# sx19_project_02_air_quality.net
KiCad netlist of a schematic drawn in EAGLE
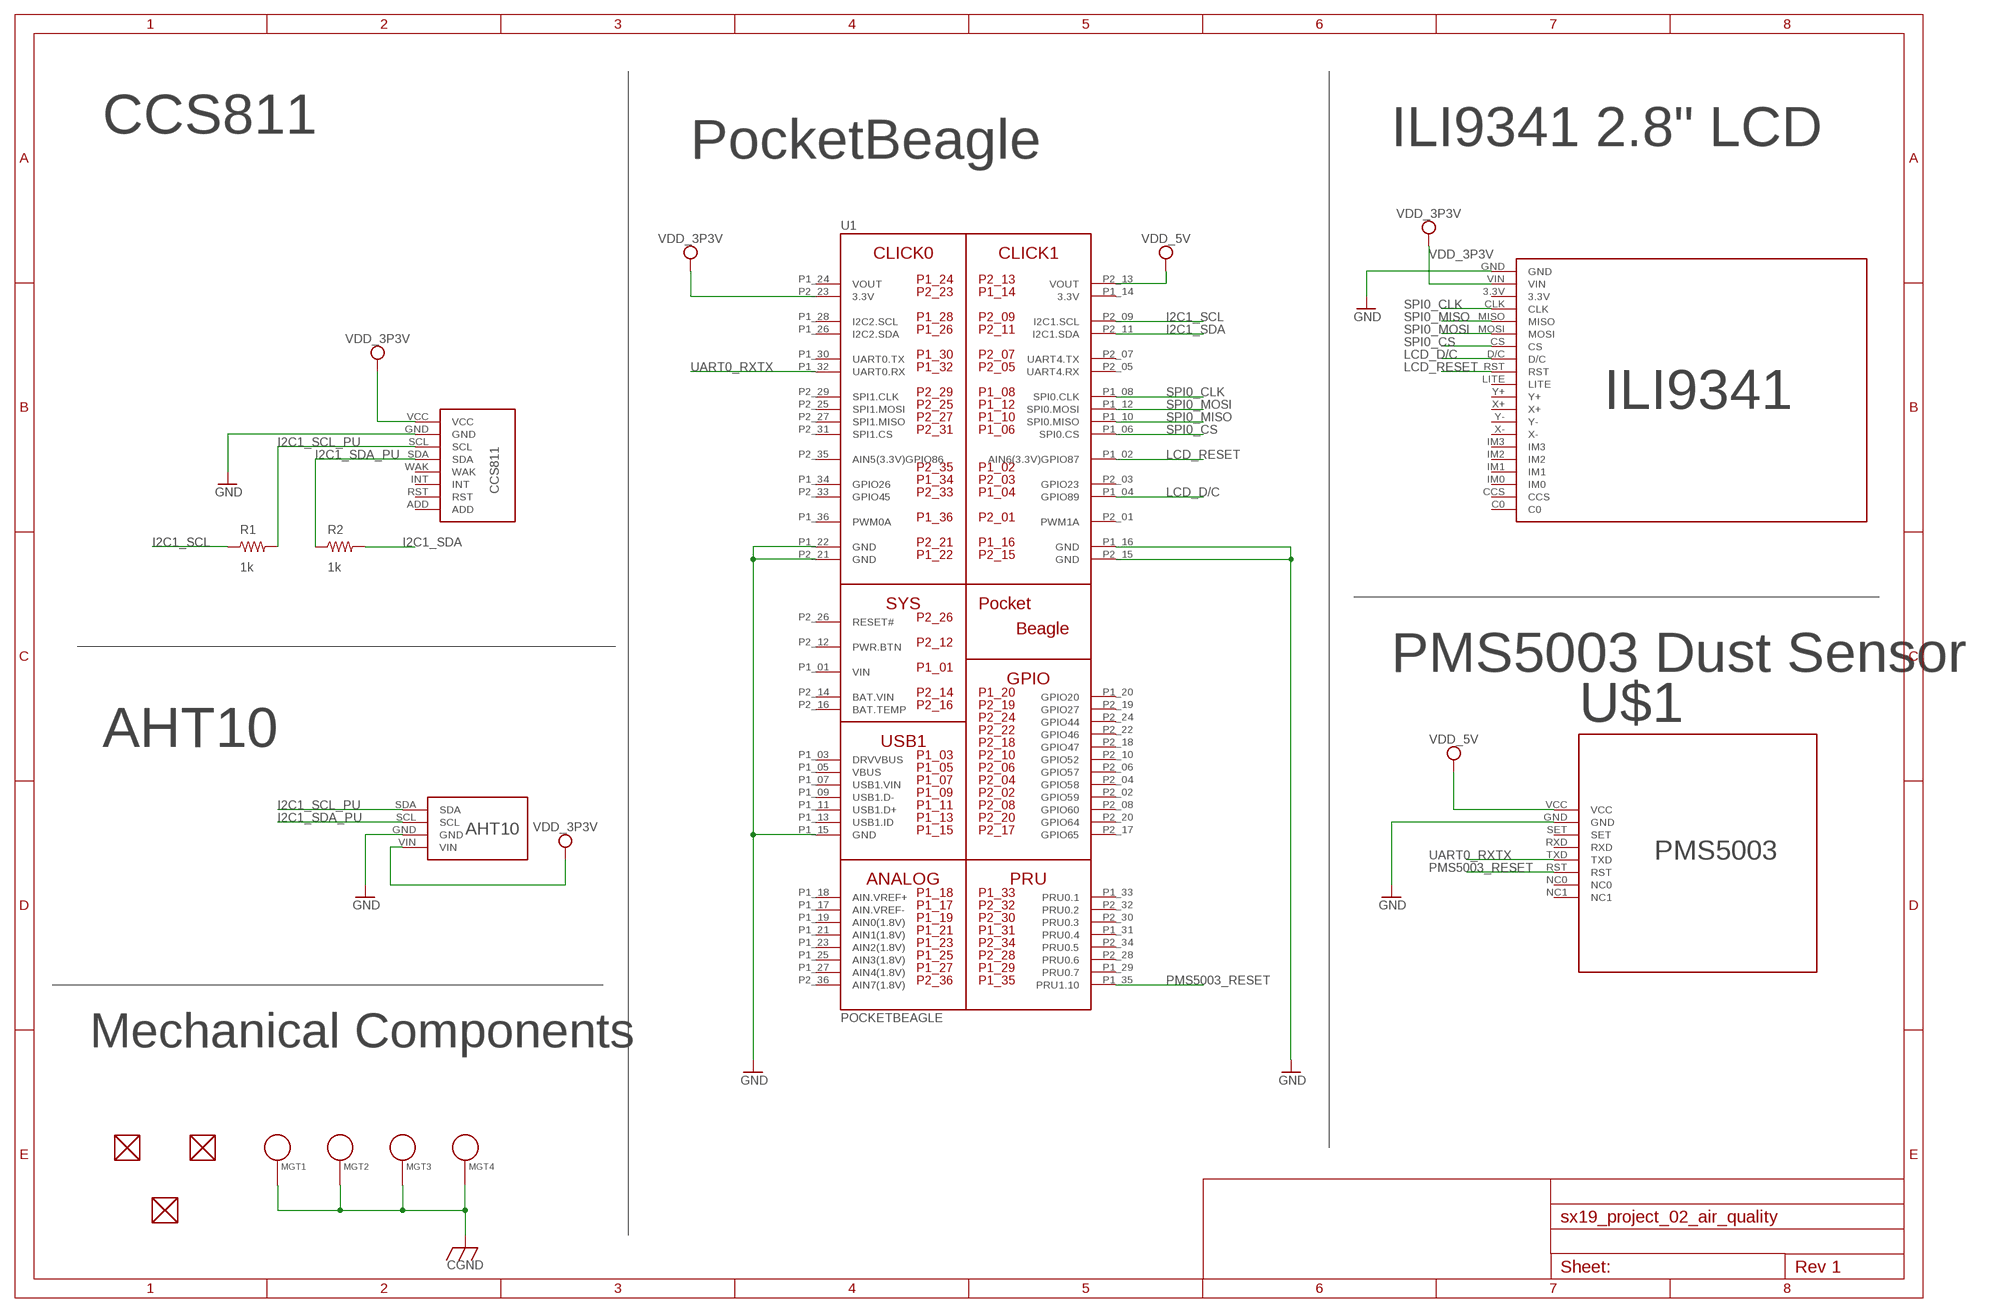
[diagram p0: schematic, sheet 1]

(export (version "E")
  (design (tool "Eeschema 10.0.6"))
  (components
    (comp (ref "B1")
      (value "AHT10")
      (footprint "eagle-import:AHT10")
      (libsource (lib "eagle-import") (part "AHT10"))
    )
    (comp (ref "B2")
      (value "CCS811")
      (footprint "eagle-import:CCS811")
      (libsource (lib "eagle-import") (part "CCS811"))
    )
    (comp (ref "B3")
      (value "ILI9341")
      (footprint "eagle-import:ILI9341")
      (libsource (lib "eagle-import") (part "ILI9341"))
    )
    (comp (ref "FUD1")
      (value "FIDUCIAL")
      (footprint "eagle-import:FIDUCIAL_40MIL")
      (libsource (lib "eagle-import") (part "FIDUCIAL"))
    )
    (comp (ref "FUD2")
      (value "FIDUCIAL")
      (footprint "eagle-import:FIDUCIAL_40MIL")
      (libsource (lib "eagle-import") (part "FIDUCIAL"))
    )
    (comp (ref "FUD3")
      (value "FIDUCIAL")
      (footprint "eagle-import:FIDUCIAL_40MIL")
      (libsource (lib "eagle-import") (part "FIDUCIAL"))
    )
    (comp (ref "MGT1")
      (value "MOUNTING_HOLE")
      (footprint "eagle-import:MOUNTING_HOLE")
      (libsource (lib "eagle-import") (part "MOUNTING_HOLE"))
    )
    (comp (ref "MGT2")
      (value "MOUNTING_HOLE")
      (footprint "eagle-import:MOUNTING_HOLE")
      (libsource (lib "eagle-import") (part "MOUNTING_HOLE"))
    )
    (comp (ref "MGT3")
      (value "MOUNTING_HOLE")
      (footprint "eagle-import:MOUNTING_HOLE")
      (libsource (lib "eagle-import") (part "MOUNTING_HOLE"))
    )
    (comp (ref "MGT4")
      (value "MOUNTING_HOLE")
      (footprint "eagle-import:MOUNTING_HOLE")
      (libsource (lib "eagle-import") (part "MOUNTING_HOLE"))
    )
    (comp (ref "R1")
      (value "1k")
      (footprint "eagle-import:R0603")
      (libsource (lib "eagle-import") (part "R_R0603"))
    )
    (comp (ref "R2")
      (value "1k")
      (footprint "eagle-import:R0603")
      (libsource (lib "eagle-import") (part "R_R0603"))
    )
    (comp (ref "U$1")
      (value "PMS5003")
      (footprint "eagle-import:PMS5003")
      (libsource (lib "eagle-import") (part "PMS5003"))
    )
    (comp (ref "U1")
      (value "POCKETBEAGLE")
      (footprint "eagle-import:POCKETBEAGLE")
      (libsource (lib "eagle-import") (part "POCKETBEAGLE"))
    )
  )
  (nets
    (net (code "1") (name "/3.3V") (class "Default")
      (node (ref "U1") (pin "P1_14") (pinfunction "3.3V_P1_14") (pintype "power_in"))
    )
    (net (code "2") (name "/BAT.VIN") (class "Default")
      (node (ref "U1") (pin "P2_14") (pinfunction "BAT.VIN_P2_14") (pintype "power_in"))
    )
    (net (code "3") (name "/I2C1_SCL") (class "Default")
      (node (ref "R1") (pin "1") (pinfunction "1_1") (pintype "passive"))
      (node (ref "U1") (pin "P2_09") (pinfunction "I2C1.SCL_P2_09") (pintype "bidirectional"))
    )
    (net (code "4") (name "/I2C1_SCL_PU") (class "Default")
      (node (ref "B1") (pin "SDA") (pinfunction "SDA_SDA") (pintype "bidirectional"))
      (node (ref "B2") (pin "SCL") (pinfunction "SCL_SCL") (pintype "bidirectional"))
      (node (ref "R1") (pin "2") (pinfunction "2_2") (pintype "passive"))
    )
    (net (code "5") (name "/I2C1_SDA") (class "Default")
      (node (ref "R2") (pin "2") (pinfunction "2_2") (pintype "passive"))
      (node (ref "U1") (pin "P2_11") (pinfunction "I2C1.SDA_P2_11") (pintype "bidirectional"))
    )
    (net (code "6") (name "/I2C1_SDA_PU") (class "Default")
      (node (ref "B1") (pin "SCL") (pinfunction "SCL_SCL") (pintype "bidirectional"))
      (node (ref "B2") (pin "SDA") (pinfunction "SDA_SDA") (pintype "bidirectional"))
      (node (ref "R2") (pin "1") (pinfunction "1_1") (pintype "passive"))
    )
    (net (code "7") (name "/LCD_D{slash}C") (class "Default")
      (node (ref "B3") (pin "D/C") (pinfunction "D/C_D/C") (pintype "bidirectional"))
      (node (ref "U1") (pin "P1_04") (pinfunction "GPIO89_P1_04") (pintype "bidirectional"))
    )
    (net (code "8") (name "/LCD_RESET") (class "Default")
      (node (ref "B3") (pin "RST") (pinfunction "RST_RST") (pintype "bidirectional"))
      (node (ref "U1") (pin "P1_02") (pinfunction "AIN6(3.3V)GPIO87_P1_02") (pintype "bidirectional"))
    )
    (net (code "9") (name "/PMS5003_RESET") (class "Default")
      (node (ref "U$1") (pin "RST") (pinfunction "RST_RST") (pintype "bidirectional"))
      (node (ref "U1") (pin "P1_35") (pinfunction "PRU1.10_P1_35") (pintype "bidirectional"))
    )
    (net (code "10") (name "/SPI0_CLK") (class "Default")
      (node (ref "B3") (pin "CLK") (pinfunction "CLK_CLK") (pintype "bidirectional"))
      (node (ref "U1") (pin "P1_08") (pinfunction "SPI0.CLK_P1_08") (pintype "bidirectional"))
    )
    (net (code "11") (name "/SPI0_CS") (class "Default")
      (node (ref "B3") (pin "CS") (pinfunction "CS_CS") (pintype "bidirectional"))
      (node (ref "U1") (pin "P1_06") (pinfunction "SPI0.CS_P1_06") (pintype "bidirectional"))
    )
    (net (code "12") (name "/SPI0_MISO") (class "Default")
      (node (ref "B3") (pin "MISO") (pinfunction "MISO_MISO") (pintype "bidirectional"))
      (node (ref "U1") (pin "P1_10") (pinfunction "SPI0.MISO_P1_10") (pintype "bidirectional"))
    )
    (net (code "13") (name "/SPI0_MOSI") (class "Default")
      (node (ref "B3") (pin "MOSI") (pinfunction "MOSI_MOSI") (pintype "bidirectional"))
      (node (ref "U1") (pin "P1_12") (pinfunction "SPI0.MOSI_P1_12") (pintype "bidirectional"))
    )
    (net (code "14") (name "/UART0_RXTX") (class "Default")
      (node (ref "U$1") (pin "TXD") (pinfunction "TXD_TXD") (pintype "bidirectional"))
      (node (ref "U1") (pin "P1_32") (pinfunction "UART0.RX_P1_32") (pintype "bidirectional"))
    )
    (net (code "15") (name "/VIN") (class "Default")
      (node (ref "U1") (pin "P1_01") (pinfunction "VIN_P1_01") (pintype "power_in"))
    )
    (net (code "16") (name "/VOUT") (class "Default")
      (node (ref "U1") (pin "P1_24") (pinfunction "VOUT_P1_24") (pintype "power_in"))
    )
    (net (code "17") (name "CGND") (class "Default")
      (node (ref "MGT1") (pin "P$1") (pinfunction "P$1_P$1") (pintype "bidirectional"))
      (node (ref "MGT2") (pin "P$1") (pinfunction "P$1_P$1") (pintype "bidirectional"))
      (node (ref "MGT3") (pin "P$1") (pinfunction "P$1_P$1") (pintype "bidirectional"))
      (node (ref "MGT4") (pin "P$1") (pinfunction "P$1_P$1") (pintype "bidirectional"))
    )
    (net (code "18") (name "GND") (class "Default")
      (node (ref "B1") (pin "GND") (pinfunction "GND_GND") (pintype "bidirectional"))
      (node (ref "B2") (pin "GND") (pinfunction "GND_GND") (pintype "bidirectional"))
      (node (ref "B3") (pin "GND") (pinfunction "GND_GND") (pintype "bidirectional"))
      (node (ref "U$1") (pin "GND") (pinfunction "GND_GND") (pintype "bidirectional"))
      (node (ref "U1") (pin "P1_15") (pinfunction "GND_P1_15") (pintype "bidirectional"))
      (node (ref "U1") (pin "P1_16") (pinfunction "GND_P1_16") (pintype "power_in"))
      (node (ref "U1") (pin "P1_22") (pinfunction "GND_P1_22") (pintype "power_in"))
      (node (ref "U1") (pin "P2_15") (pinfunction "GND_P2_15") (pintype "power_in"))
      (node (ref "U1") (pin "P2_21") (pinfunction "GND_P2_21") (pintype "power_in"))
    )
    (net (code "19") (name "VDD_3P3V") (class "Default")
      (node (ref "B1") (pin "VIN") (pinfunction "VIN_VIN") (pintype "bidirectional"))
      (node (ref "B2") (pin "VCC") (pinfunction "VCC_VCC") (pintype "bidirectional"))
      (node (ref "B3") (pin "VIN") (pinfunction "VIN_VIN") (pintype "bidirectional"))
      (node (ref "U1") (pin "P2_23") (pinfunction "3.3V_P2_23") (pintype "power_in"))
    )
    (net (code "20") (name "VDD_5V") (class "Default")
      (node (ref "U$1") (pin "VCC") (pinfunction "VCC_VCC") (pintype "bidirectional"))
      (node (ref "U1") (pin "P2_13") (pinfunction "VOUT_P2_13") (pintype "power_in"))
    )
    (net (code "21") (name "unconnected-(B2-PadADD)") (class "Default")
      (node (ref "B2") (pin "ADD") (pinfunction "ADD_ADD") (pintype "bidirectional"))
    )
    (net (code "22") (name "unconnected-(B2-PadINT)") (class "Default")
      (node (ref "B2") (pin "INT") (pinfunction "INT_INT") (pintype "bidirectional"))
    )
    (net (code "23") (name "unconnected-(B2-PadRST)") (class "Default")
      (node (ref "B2") (pin "RST") (pinfunction "RST_RST") (pintype "bidirectional"))
    )
    (net (code "24") (name "unconnected-(B2-PadWAK)") (class "Default")
      (node (ref "B2") (pin "WAK") (pinfunction "WAK_WAK") (pintype "bidirectional"))
    )
    (net (code "25") (name "unconnected-(B3-Pad3.3V)") (class "Default")
      (node (ref "B3") (pin "3.3V") (pinfunction "3.3V_3.3V") (pintype "bidirectional"))
    )
    (net (code "26") (name "unconnected-(B3-PadC0)") (class "Default")
      (node (ref "B3") (pin "C0") (pinfunction "C0_C0") (pintype "bidirectional"))
    )
    (net (code "27") (name "unconnected-(B3-PadCCS)") (class "Default")
      (node (ref "B3") (pin "CCS") (pinfunction "CCS_CCS") (pintype "bidirectional"))
    )
    (net (code "28") (name "unconnected-(B3-PadIM0)") (class "Default")
      (node (ref "B3") (pin "IM0") (pinfunction "IM0_IM0") (pintype "bidirectional"))
    )
    (net (code "29") (name "unconnected-(B3-PadIM1)") (class "Default")
      (node (ref "B3") (pin "IM1") (pinfunction "IM1_IM1") (pintype "bidirectional"))
    )
    (net (code "30") (name "unconnected-(B3-PadIM2)") (class "Default")
      (node (ref "B3") (pin "IM2") (pinfunction "IM2_IM2") (pintype "bidirectional"))
    )
    (net (code "31") (name "unconnected-(B3-PadIM3)") (class "Default")
      (node (ref "B3") (pin "IM3") (pinfunction "IM3_IM3") (pintype "bidirectional"))
    )
    (net (code "32") (name "unconnected-(B3-PadLITE)") (class "Default")
      (node (ref "B3") (pin "LITE") (pinfunction "LITE_LITE") (pintype "bidirectional"))
    )
    (net (code "33") (name "unconnected-(B3-PadX+)") (class "Default")
      (node (ref "B3") (pin "X+") (pinfunction "X+_X+") (pintype "bidirectional"))
    )
    (net (code "34") (name "unconnected-(B3-PadX-)") (class "Default")
      (node (ref "B3") (pin "X-") (pinfunction "X-_X-") (pintype "bidirectional"))
    )
    (net (code "35") (name "unconnected-(B3-PadY+)") (class "Default")
      (node (ref "B3") (pin "Y+") (pinfunction "Y+_Y+") (pintype "bidirectional"))
    )
    (net (code "36") (name "unconnected-(B3-PadY-)") (class "Default")
      (node (ref "B3") (pin "Y-") (pinfunction "Y-_Y-") (pintype "bidirectional"))
    )
    (net (code "37") (name "unconnected-(FUD1-PadP$1)") (class "Default")
      (node (ref "FUD1") (pin "P$1") (pinfunction "P$1_P$1") (pintype "no_connect"))
    )
    (net (code "38") (name "unconnected-(FUD2-PadP$1)") (class "Default")
      (node (ref "FUD2") (pin "P$1") (pinfunction "P$1_P$1") (pintype "no_connect"))
    )
    (net (code "39") (name "unconnected-(FUD3-PadP$1)") (class "Default")
      (node (ref "FUD3") (pin "P$1") (pinfunction "P$1_P$1") (pintype "no_connect"))
    )
    (net (code "40") (name "unconnected-(U$1-PadNC0)") (class "Default")
      (node (ref "U$1") (pin "NC0") (pinfunction "NC0_NC0") (pintype "bidirectional"))
    )
    (net (code "41") (name "unconnected-(U$1-PadNC1)") (class "Default")
      (node (ref "U$1") (pin "NC1") (pinfunction "NC1_NC1") (pintype "bidirectional"))
    )
    (net (code "42") (name "unconnected-(U$1-PadRXD)") (class "Default")
      (node (ref "U$1") (pin "RXD") (pinfunction "RXD_RXD") (pintype "bidirectional"))
    )
    (net (code "43") (name "unconnected-(U$1-PadSET)") (class "Default")
      (node (ref "U$1") (pin "SET") (pinfunction "SET_SET") (pintype "bidirectional"))
    )
    (net (code "44") (name "unconnected-(U1-AIN.VREF+-PadP1_18)") (class "Default")
      (node (ref "U1") (pin "P1_18") (pinfunction "AIN.VREF+_P1_18") (pintype "input"))
    )
    (net (code "45") (name "unconnected-(U1-AIN.VREF--PadP1_17)") (class "Default")
      (node (ref "U1") (pin "P1_17") (pinfunction "AIN.VREF-_P1_17") (pintype "input"))
    )
    (net (code "46") (name "unconnected-(U1-AIN0(1.8V)-PadP1_19)") (class "Default")
      (node (ref "U1") (pin "P1_19") (pinfunction "AIN0(1.8V)_P1_19") (pintype "input"))
    )
    (net (code "47") (name "unconnected-(U1-AIN1(1.8V)-PadP1_21)") (class "Default")
      (node (ref "U1") (pin "P1_21") (pinfunction "AIN1(1.8V)_P1_21") (pintype "input"))
    )
    (net (code "48") (name "unconnected-(U1-AIN2(1.8V)-PadP1_23)") (class "Default")
      (node (ref "U1") (pin "P1_23") (pinfunction "AIN2(1.8V)_P1_23") (pintype "input"))
    )
    (net (code "49") (name "unconnected-(U1-AIN3(1.8V)-PadP1_25)") (class "Default")
      (node (ref "U1") (pin "P1_25") (pinfunction "AIN3(1.8V)_P1_25") (pintype "input"))
    )
    (net (code "50") (name "unconnected-(U1-AIN4(1.8V)-PadP1_27)") (class "Default")
      (node (ref "U1") (pin "P1_27") (pinfunction "AIN4(1.8V)_P1_27") (pintype "input"))
    )
    (net (code "51") (name "unconnected-(U1-AIN5(3.3V)GPIO86-PadP2_35)") (class "Default")
      (node (ref "U1") (pin "P2_35") (pinfunction "AIN5(3.3V)GPIO86_P2_35") (pintype "bidirectional"))
    )
    (net (code "52") (name "unconnected-(U1-AIN7(1.8V)-PadP2_36)") (class "Default")
      (node (ref "U1") (pin "P2_36") (pinfunction "AIN7(1.8V)_P2_36") (pintype "input"))
    )
    (net (code "53") (name "unconnected-(U1-BAT.TEMP-PadP2_16)") (class "Default")
      (node (ref "U1") (pin "P2_16") (pinfunction "BAT.TEMP_P2_16") (pintype "input"))
    )
    (net (code "54") (name "unconnected-(U1-DRVVBUS-PadP1_03)") (class "Default")
      (node (ref "U1") (pin "P1_03") (pinfunction "DRVVBUS_P1_03") (pintype "bidirectional"))
    )
    (net (code "55") (name "unconnected-(U1-GPIO20-PadP1_20)") (class "Default")
      (node (ref "U1") (pin "P1_20") (pinfunction "GPIO20_P1_20") (pintype "bidirectional"))
    )
    (net (code "56") (name "unconnected-(U1-GPIO23-PadP2_03)") (class "Default")
      (node (ref "U1") (pin "P2_03") (pinfunction "GPIO23_P2_03") (pintype "bidirectional"))
    )
    (net (code "57") (name "unconnected-(U1-GPIO26-PadP1_34)") (class "Default")
      (node (ref "U1") (pin "P1_34") (pinfunction "GPIO26_P1_34") (pintype "bidirectional"))
    )
    (net (code "58") (name "unconnected-(U1-GPIO27-PadP2_19)") (class "Default")
      (node (ref "U1") (pin "P2_19") (pinfunction "GPIO27_P2_19") (pintype "bidirectional"))
    )
    (net (code "59") (name "unconnected-(U1-GPIO44-PadP2_24)") (class "Default")
      (node (ref "U1") (pin "P2_24") (pinfunction "GPIO44_P2_24") (pintype "bidirectional"))
    )
    (net (code "60") (name "unconnected-(U1-GPIO45-PadP2_33)") (class "Default")
      (node (ref "U1") (pin "P2_33") (pinfunction "GPIO45_P2_33") (pintype "bidirectional"))
    )
    (net (code "61") (name "unconnected-(U1-GPIO46-PadP2_22)") (class "Default")
      (node (ref "U1") (pin "P2_22") (pinfunction "GPIO46_P2_22") (pintype "bidirectional"))
    )
    (net (code "62") (name "unconnected-(U1-GPIO47-PadP2_18)") (class "Default")
      (node (ref "U1") (pin "P2_18") (pinfunction "GPIO47_P2_18") (pintype "bidirectional"))
    )
    (net (code "63") (name "unconnected-(U1-GPIO52-PadP2_10)") (class "Default")
      (node (ref "U1") (pin "P2_10") (pinfunction "GPIO52_P2_10") (pintype "bidirectional"))
    )
    (net (code "64") (name "unconnected-(U1-GPIO57-PadP2_06)") (class "Default")
      (node (ref "U1") (pin "P2_06") (pinfunction "GPIO57_P2_06") (pintype "bidirectional"))
    )
    (net (code "65") (name "unconnected-(U1-GPIO58-PadP2_04)") (class "Default")
      (node (ref "U1") (pin "P2_04") (pinfunction "GPIO58_P2_04") (pintype "bidirectional"))
    )
    (net (code "66") (name "unconnected-(U1-GPIO59-PadP2_02)") (class "Default")
      (node (ref "U1") (pin "P2_02") (pinfunction "GPIO59_P2_02") (pintype "bidirectional"))
    )
    (net (code "67") (name "unconnected-(U1-GPIO60-PadP2_08)") (class "Default")
      (node (ref "U1") (pin "P2_08") (pinfunction "GPIO60_P2_08") (pintype "bidirectional"))
    )
    (net (code "68") (name "unconnected-(U1-GPIO64-PadP2_20)") (class "Default")
      (node (ref "U1") (pin "P2_20") (pinfunction "GPIO64_P2_20") (pintype "bidirectional"))
    )
    (net (code "69") (name "unconnected-(U1-GPIO65-PadP2_17)") (class "Default")
      (node (ref "U1") (pin "P2_17") (pinfunction "GPIO65_P2_17") (pintype "bidirectional"))
    )
    (net (code "70") (name "unconnected-(U1-I2C2.SCL-PadP1_28)") (class "Default")
      (node (ref "U1") (pin "P1_28") (pinfunction "I2C2.SCL_P1_28") (pintype "bidirectional"))
    )
    (net (code "71") (name "unconnected-(U1-I2C2.SDA-PadP1_26)") (class "Default")
      (node (ref "U1") (pin "P1_26") (pinfunction "I2C2.SDA_P1_26") (pintype "bidirectional"))
    )
    (net (code "72") (name "unconnected-(U1-PRU0.1-PadP1_33)") (class "Default")
      (node (ref "U1") (pin "P1_33") (pinfunction "PRU0.1_P1_33") (pintype "bidirectional"))
    )
    (net (code "73") (name "unconnected-(U1-PRU0.2-PadP2_32)") (class "Default")
      (node (ref "U1") (pin "P2_32") (pinfunction "PRU0.2_P2_32") (pintype "bidirectional"))
    )
    (net (code "74") (name "unconnected-(U1-PRU0.3-PadP2_30)") (class "Default")
      (node (ref "U1") (pin "P2_30") (pinfunction "PRU0.3_P2_30") (pintype "bidirectional"))
    )
    (net (code "75") (name "unconnected-(U1-PRU0.4-PadP1_31)") (class "Default")
      (node (ref "U1") (pin "P1_31") (pinfunction "PRU0.4_P1_31") (pintype "bidirectional"))
    )
    (net (code "76") (name "unconnected-(U1-PRU0.5-PadP2_34)") (class "Default")
      (node (ref "U1") (pin "P2_34") (pinfunction "PRU0.5_P2_34") (pintype "bidirectional"))
    )
    (net (code "77") (name "unconnected-(U1-PRU0.6-PadP2_28)") (class "Default")
      (node (ref "U1") (pin "P2_28") (pinfunction "PRU0.6_P2_28") (pintype "bidirectional"))
    )
    (net (code "78") (name "unconnected-(U1-PRU0.7-PadP1_29)") (class "Default")
      (node (ref "U1") (pin "P1_29") (pinfunction "PRU0.7_P1_29") (pintype "bidirectional"))
    )
    (net (code "79") (name "unconnected-(U1-PWM0A-PadP1_36)") (class "Default")
      (node (ref "U1") (pin "P1_36") (pinfunction "PWM0A_P1_36") (pintype "bidirectional"))
    )
    (net (code "80") (name "unconnected-(U1-PWM1A-PadP2_01)") (class "Default")
      (node (ref "U1") (pin "P2_01") (pinfunction "PWM1A_P2_01") (pintype "bidirectional"))
    )
    (net (code "81") (name "unconnected-(U1-PWR.BTN-PadP2_12)") (class "Default")
      (node (ref "U1") (pin "P2_12") (pinfunction "PWR.BTN_P2_12") (pintype "input"))
    )
    (net (code "82") (name "unconnected-(U1-RESET#-PadP2_26)") (class "Default")
      (node (ref "U1") (pin "P2_26") (pinfunction "RESET#_P2_26") (pintype "input"))
    )
    (net (code "83") (name "unconnected-(U1-SPI1.CLK-PadP2_29)") (class "Default")
      (node (ref "U1") (pin "P2_29") (pinfunction "SPI1.CLK_P2_29") (pintype "bidirectional"))
    )
    (net (code "84") (name "unconnected-(U1-SPI1.CS-PadP2_31)") (class "Default")
      (node (ref "U1") (pin "P2_31") (pinfunction "SPI1.CS_P2_31") (pintype "bidirectional"))
    )
    (net (code "85") (name "unconnected-(U1-SPI1.MISO-PadP2_27)") (class "Default")
      (node (ref "U1") (pin "P2_27") (pinfunction "SPI1.MISO_P2_27") (pintype "bidirectional"))
    )
    (net (code "86") (name "unconnected-(U1-SPI1.MOSI-PadP2_25)") (class "Default")
      (node (ref "U1") (pin "P2_25") (pinfunction "SPI1.MOSI_P2_25") (pintype "bidirectional"))
    )
    (net (code "87") (name "unconnected-(U1-UART0.TX-PadP1_30)") (class "Default")
      (node (ref "U1") (pin "P1_30") (pinfunction "UART0.TX_P1_30") (pintype "bidirectional"))
    )
    (net (code "88") (name "unconnected-(U1-UART4.RX-PadP2_05)") (class "Default")
      (node (ref "U1") (pin "P2_05") (pinfunction "UART4.RX_P2_05") (pintype "bidirectional"))
    )
    (net (code "89") (name "unconnected-(U1-UART4.TX-PadP2_07)") (class "Default")
      (node (ref "U1") (pin "P2_07") (pinfunction "UART4.TX_P2_07") (pintype "bidirectional"))
    )
    (net (code "90") (name "unconnected-(U1-USB1.D+-PadP1_11)") (class "Default")
      (node (ref "U1") (pin "P1_11") (pinfunction "USB1.D+_P1_11") (pintype "bidirectional"))
    )
    (net (code "91") (name "unconnected-(U1-USB1.D--PadP1_09)") (class "Default")
      (node (ref "U1") (pin "P1_09") (pinfunction "USB1.D-_P1_09") (pintype "bidirectional"))
    )
    (net (code "92") (name "unconnected-(U1-USB1.ID-PadP1_13)") (class "Default")
      (node (ref "U1") (pin "P1_13") (pinfunction "USB1.ID_P1_13") (pintype "bidirectional"))
    )
    (net (code "93") (name "unconnected-(U1-USB1.VIN-PadP1_07)") (class "Default")
      (node (ref "U1") (pin "P1_07") (pinfunction "USB1.VIN_P1_07") (pintype "bidirectional"))
    )
    (net (code "94") (name "unconnected-(U1-VBUS-PadP1_05)") (class "Default")
      (node (ref "U1") (pin "P1_05") (pinfunction "VBUS_P1_05") (pintype "bidirectional"))
    )
  )
)
